# VF_GS_PCB.net
KiCad netlist of a schematic drawn in EAGLE
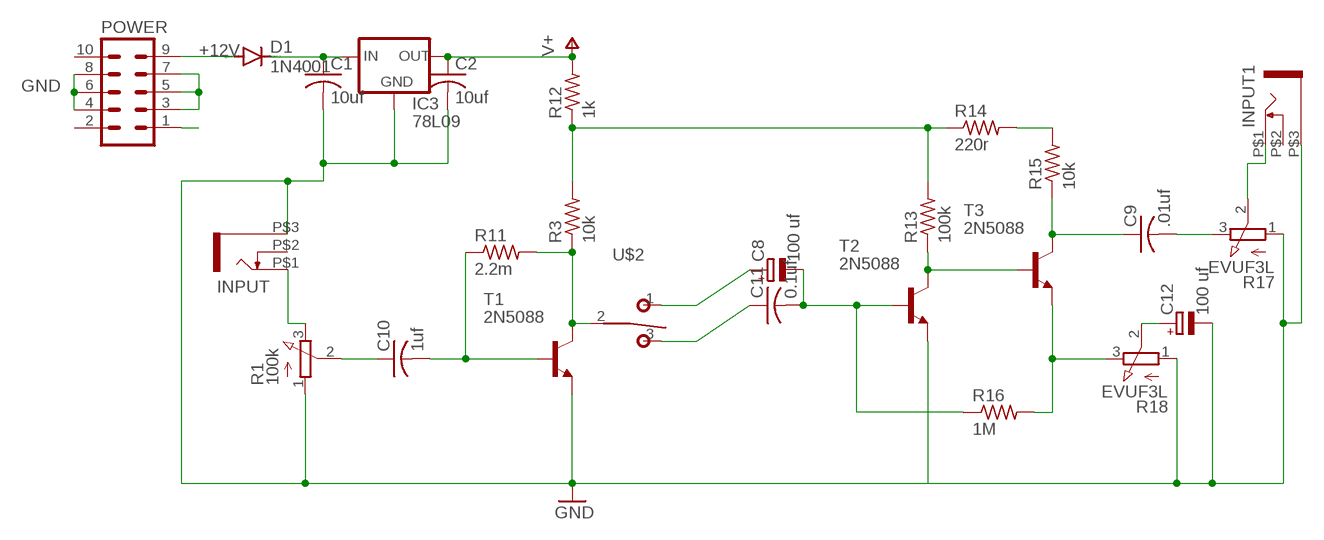
[diagram p0: schematic, sheet 1]

(export (version "E")
  (design (tool "Eeschema 10.0.6"))
  (components
    (comp (ref "C1")
      (value "10uf")
      (footprint "eagle-import:C050-025X075")
      (libsource (lib "eagle-import") (part "C-US050-025X075"))
    )
    (comp (ref "C2")
      (value "10uf")
      (footprint "eagle-import:C050-025X075")
      (libsource (lib "eagle-import") (part "C-US050-025X075"))
    )
    (comp (ref "C8")
      (value "100 uf")
      (footprint "eagle-import:E2,5-6")
      (libsource (lib "eagle-import") (part "CPOL-EUE2.5-6"))
    )
    (comp (ref "C9")
      (value ".01uf")
      (footprint "eagle-import:C050-025X075")
      (libsource (lib "eagle-import") (part "C-US050-025X075"))
    )
    (comp (ref "C10")
      (value "1uf")
      (footprint "eagle-import:C050-025X075")
      (libsource (lib "eagle-import") (part "C-US050-025X075"))
    )
    (comp (ref "C11")
      (value "0.1uf")
      (footprint "eagle-import:C050-025X075")
      (libsource (lib "eagle-import") (part "C-US050-025X075"))
    )
    (comp (ref "C12")
      (value "100 uf")
      (footprint "eagle-import:E2,5-6")
      (libsource (lib "eagle-import") (part "CPOL-EUE2.5-6"))
    )
    (comp (ref "D1")
      (value "1N4001")
      (footprint "eagle-import:DO41-10")
      (libsource (lib "eagle-import") (part "1N4004"))
    )
    (comp (ref "IC3")
      (value "78L09")
      (footprint "eagle-import:78LXX")
      (libsource (lib "eagle-import") (part "78LXX"))
    )
    (comp (ref "INPUT")
      (value "WQP-PJ301M-12_JACK")
      (footprint "eagle-import:WQP-PJ301M-12_JACK")
      (libsource (lib "eagle-import") (part "WQP-PJ301M-12_JACK"))
    )
    (comp (ref "INPUT1")
      (value "WQP-PJ301M-12_JACK")
      (footprint "eagle-import:WQP-PJ301M-12_JACK")
      (libsource (lib "eagle-import") (part "WQP-PJ301M-12_JACK"))
    )
    (comp (ref "POWER")
      (value "10_PIN_HEADER")
      (footprint "eagle-import:MA05-2")
      (libsource (lib "eagle-import") (part "10_PIN_HEADER"))
    )
    (comp (ref "R1")
      (value "100k")
      (footprint "eagle-import:EVUFXL")
      (libsource (lib "eagle-import") (part "EVULF3"))
    )
    (comp (ref "R3")
      (value "10k")
      (footprint "eagle-import:0207_7")
      (libsource (lib "eagle-import") (part "R-US_0207/7"))
    )
    (comp (ref "R11")
      (value "2.2m")
      (footprint "eagle-import:0207_7")
      (libsource (lib "eagle-import") (part "R-US_0207/7"))
    )
    (comp (ref "R12")
      (value "1k")
      (footprint "eagle-import:0207_7")
      (libsource (lib "eagle-import") (part "R-US_0207/7"))
    )
    (comp (ref "R13")
      (value "100k")
      (footprint "eagle-import:0207_7")
      (libsource (lib "eagle-import") (part "R-US_0207/7"))
    )
    (comp (ref "R14")
      (value "220r")
      (footprint "eagle-import:0207_7")
      (libsource (lib "eagle-import") (part "R-US_0207/7"))
    )
    (comp (ref "R15")
      (value "10k")
      (footprint "eagle-import:0207_7")
      (libsource (lib "eagle-import") (part "rcl_334_R-US_0207/7"))
    )
    (comp (ref "R16")
      (value "1M")
      (footprint "eagle-import:0207_7")
      (libsource (lib "eagle-import") (part "rcl_334_R-US_0207/7"))
    )
    (comp (ref "R17")
      (value "EVUF3L")
      (footprint "eagle-import:EVUFXL")
      (libsource (lib "eagle-import") (part "EVULF3"))
    )
    (comp (ref "R18")
      (value "EVUF3L")
      (footprint "eagle-import:EVUFXL")
      (libsource (lib "eagle-import") (part "EVULF3"))
    )
    (comp (ref "T1")
      (value "2N5088")
      (footprint "eagle-import:TO92")
      (libsource (lib "eagle-import") (part "2N5088"))
    )
    (comp (ref "T2")
      (value "2N5088")
      (footprint "eagle-import:TO92")
      (libsource (lib "eagle-import") (part "2N5088"))
    )
    (comp (ref "T3")
      (value "2N5088")
      (footprint "eagle-import:TO92")
      (libsource (lib "eagle-import") (part "transistor_402_2N5088"))
    )
    (comp (ref "U$2")
      (value "T-80-T-SPDT-ON-OFF-ON")
      (footprint "eagle-import:M9040P")
      (libsource (lib "eagle-import") (part "T-80-T-SPDT-ON-OFF-ON"))
    )
  )
  (nets
    (net (code "1") (name "/+12V") (class "Default")
      (node (ref "C1") (pin "1") (pinfunction "1_1") (pintype "passive"))
      (node (ref "D1") (pin "C") (pinfunction "C_C") (pintype "passive"))
      (node (ref "IC3") (pin "IN") (pinfunction "IN_IN") (pintype "input"))
    )
    (net (code "2") (name "GND") (class "Default")
      (node (ref "C1") (pin "2") (pinfunction "2_2") (pintype "passive"))
      (node (ref "C12") (pin "-") (pinfunction "-_-") (pintype "passive"))
      (node (ref "C2") (pin "2") (pinfunction "2_2") (pintype "passive"))
      (node (ref "IC3") (pin "GND") (pinfunction "GND_GND") (pintype "input"))
      (node (ref "INPUT") (pin "P$3") (pinfunction "1_P$3") (pintype "passive"))
      (node (ref "INPUT1") (pin "P$3") (pinfunction "1_P$3") (pintype "passive"))
      (node (ref "POWER") (pin "3") (pinfunction "3_3") (pintype "passive"))
      (node (ref "POWER") (pin "4") (pinfunction "4_4") (pintype "passive"))
      (node (ref "POWER") (pin "5") (pinfunction "5_5") (pintype "passive"))
      (node (ref "POWER") (pin "6") (pinfunction "6_6") (pintype "passive"))
      (node (ref "POWER") (pin "7") (pinfunction "7_7") (pintype "passive"))
      (node (ref "POWER") (pin "8") (pinfunction "8_8") (pintype "passive"))
      (node (ref "R1") (pin "1") (pinfunction "A_1") (pintype "passive"))
      (node (ref "R17") (pin "1") (pinfunction "A_1") (pintype "passive"))
      (node (ref "R18") (pin "1") (pinfunction "A_1") (pintype "passive"))
      (node (ref "T1") (pin "3") (pinfunction "E_3") (pintype "passive"))
      (node (ref "T2") (pin "3") (pinfunction "E_3") (pintype "passive"))
    )
    (net (code "3") (name "Net-(D1-PadA)") (class "Default")
      (node (ref "D1") (pin "A") (pinfunction "A_A") (pintype "passive"))
      (node (ref "POWER") (pin "9") (pinfunction "9_9") (pintype "passive"))
    )
    (net (code "4") (name "Net-(INPUT-2)") (class "Default")
      (node (ref "INPUT") (pin "P$1") (pinfunction "2_P$1") (pintype "passive"))
      (node (ref "R1") (pin "3") (pinfunction "E_3") (pintype "passive"))
    )
    (net (code "5") (name "Net-(INPUT1-2)") (class "Default")
      (node (ref "INPUT1") (pin "P$1") (pinfunction "2_P$1") (pintype "passive"))
      (node (ref "R17") (pin "2") (pinfunction "S_2") (pintype "passive"))
    )
    (net (code "6") (name "Net-(R1-S)") (class "Default")
      (node (ref "C10") (pin "1") (pinfunction "1_1") (pintype "passive"))
      (node (ref "R1") (pin "2") (pinfunction "S_2") (pintype "passive"))
    )
    (net (code "7") (name "Net-(R12-Pad1)") (class "Default")
      (node (ref "R12") (pin "1") (pinfunction "1_1") (pintype "passive"))
      (node (ref "R13") (pin "2") (pinfunction "2_2") (pintype "passive"))
      (node (ref "R14") (pin "1") (pinfunction "1_1") (pintype "passive"))
      (node (ref "R3") (pin "2") (pinfunction "2_2") (pintype "passive"))
    )
    (net (code "8") (name "Net-(R14-Pad2)") (class "Default")
      (node (ref "R14") (pin "2") (pinfunction "2_2") (pintype "passive"))
      (node (ref "R15") (pin "2") (pinfunction "2_2") (pintype "passive"))
    )
    (net (code "9") (name "Net-(R17-E)") (class "Default")
      (node (ref "C9") (pin "2") (pinfunction "2_2") (pintype "passive"))
      (node (ref "R17") (pin "3") (pinfunction "E_3") (pintype "passive"))
    )
    (net (code "10") (name "Net-(R18-E)") (class "Default")
      (node (ref "R16") (pin "2") (pinfunction "2_2") (pintype "passive"))
      (node (ref "R18") (pin "3") (pinfunction "E_3") (pintype "passive"))
      (node (ref "T3") (pin "3") (pinfunction "E_3") (pintype "passive"))
    )
    (net (code "11") (name "Net-(R18-S)") (class "Default")
      (node (ref "C12") (pin "+") (pinfunction "+_+") (pintype "passive"))
      (node (ref "R18") (pin "2") (pinfunction "S_2") (pintype "passive"))
    )
    (net (code "12") (name "Net-(T1-B)") (class "Default")
      (node (ref "C10") (pin "2") (pinfunction "2_2") (pintype "passive"))
      (node (ref "R11") (pin "1") (pinfunction "1_1") (pintype "passive"))
      (node (ref "T1") (pin "2") (pinfunction "B_2") (pintype "passive"))
    )
    (net (code "13") (name "Net-(T1-C)") (class "Default")
      (node (ref "R11") (pin "2") (pinfunction "2_2") (pintype "passive"))
      (node (ref "R3") (pin "1") (pinfunction "1_1") (pintype "passive"))
      (node (ref "T1") (pin "1") (pinfunction "C_1") (pintype "passive"))
      (node (ref "U$2") (pin "2") (pinfunction "P_2") (pintype "passive"))
    )
    (net (code "14") (name "Net-(T2-B)") (class "Default")
      (node (ref "C11") (pin "2") (pinfunction "2_2") (pintype "passive"))
      (node (ref "C8") (pin "-") (pinfunction "-_-") (pintype "passive"))
      (node (ref "R16") (pin "1") (pinfunction "1_1") (pintype "passive"))
      (node (ref "T2") (pin "2") (pinfunction "B_2") (pintype "passive"))
    )
    (net (code "15") (name "Net-(T2-C)") (class "Default")
      (node (ref "R13") (pin "1") (pinfunction "1_1") (pintype "passive"))
      (node (ref "T2") (pin "1") (pinfunction "C_1") (pintype "passive"))
      (node (ref "T3") (pin "2") (pinfunction "B_2") (pintype "passive"))
    )
    (net (code "16") (name "Net-(T3-C)") (class "Default")
      (node (ref "C9") (pin "1") (pinfunction "1_1") (pintype "passive"))
      (node (ref "R15") (pin "1") (pinfunction "1_1") (pintype "passive"))
      (node (ref "T3") (pin "1") (pinfunction "C_1") (pintype "passive"))
    )
    (net (code "17") (name "Net-(U$2-O)") (class "Default")
      (node (ref "C8") (pin "+") (pinfunction "+_+") (pintype "passive"))
      (node (ref "U$2") (pin "1") (pinfunction "O_1") (pintype "passive"))
    )
    (net (code "18") (name "Net-(U$2-S)") (class "Default")
      (node (ref "C11") (pin "1") (pinfunction "1_1") (pintype "passive"))
      (node (ref "U$2") (pin "3") (pinfunction "S_3") (pintype "passive"))
    )
    (net (code "19") (name "V+") (class "Default")
      (node (ref "C2") (pin "1") (pinfunction "1_1") (pintype "passive"))
      (node (ref "IC3") (pin "OUT") (pinfunction "OUT_OUT") (pintype "passive"))
      (node (ref "R12") (pin "2") (pinfunction "2_2") (pintype "passive"))
    )
    (net (code "20") (name "unconnected-(INPUT-3-PadP$2)") (class "Default")
      (node (ref "INPUT") (pin "P$2") (pinfunction "3_P$2") (pintype "passive"))
    )
    (net (code "21") (name "unconnected-(INPUT1-3-PadP$2)") (class "Default")
      (node (ref "INPUT1") (pin "P$2") (pinfunction "3_P$2") (pintype "passive"))
    )
    (net (code "22") (name "unconnected-(POWER-Pad1)") (class "Default")
      (node (ref "POWER") (pin "1") (pinfunction "1_1") (pintype "passive"))
    )
    (net (code "23") (name "unconnected-(POWER-Pad2)") (class "Default")
      (node (ref "POWER") (pin "2") (pinfunction "2_2") (pintype "passive"))
    )
    (net (code "24") (name "unconnected-(POWER-Pad10)") (class "Default")
      (node (ref "POWER") (pin "10") (pinfunction "10_10") (pintype "passive"))
    )
  )
)
